# FTDI.net
KiCad netlist of a schematic drawn in Altium Designer
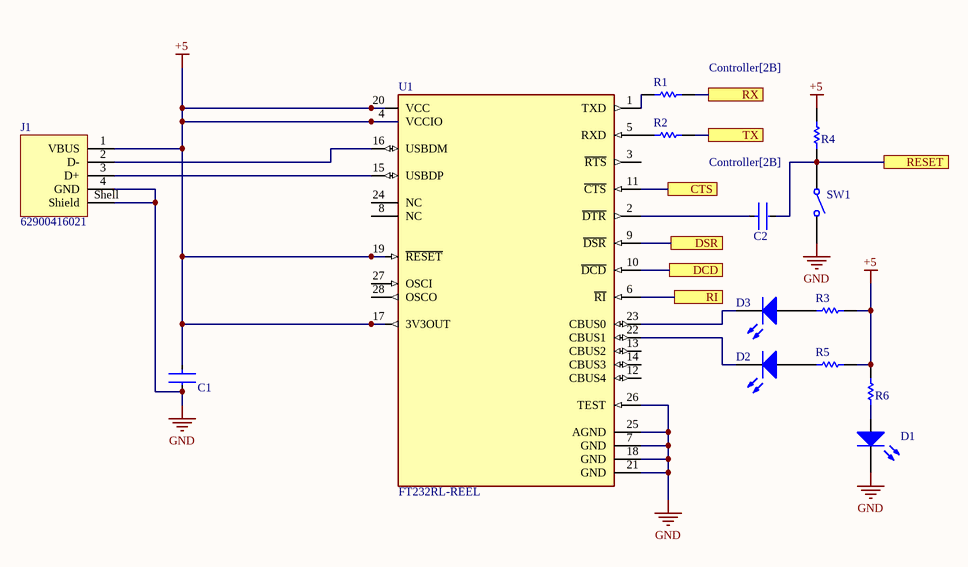
[diagram p0: FTDI.SchDoc]

(export (version "E")
  (design (tool "Eeschema 10.0.6"))
  (components
    (comp (ref "C1")
      (value "GRM188R60J106ME47D")
      (footprint "FP-GRM188-0_1-e0_2_0_55-IPC_A")
      (description "Chip Multilayer Ceramic Capacitors for General Purpose, 0603, 10uF, X5R, 15%, 20%, 6.3V")
      (fields (field (name "VOLTAGE") "6.3V") (field (name "TOLERANCE") "20%"))
      (libsource (lib "Altium Content Vault") (part "02cd4be3c70576c341d710602a673aa"))
    )
    (comp (ref "C2")
      (value "GRM188R60J106ME47D")
      (footprint "FP-GRM188-0_1-e0_2_0_55-IPC_A")
      (description "Chip Multilayer Ceramic Capacitors for General Purpose, 0603, 10uF, X5R, 15%, 20%, 6.3V")
      (fields (field (name "VOLTAGE") "6.3V") (field (name "TOLERANCE") "20%"))
      (libsource (lib "Altium Content Vault") (part "02cd4be3c70576c341d710602a673aa"))
    )
    (comp (ref "D1")
      (value "Light-Emitting Diode")
      (libsource (lib "Simulation Generic Components") (part "LED"))
    )
    (comp (ref "D2")
      (value "Light-Emitting Diode")
      (libsource (lib "Simulation Generic Components") (part "LED"))
    )
    (comp (ref "D3")
      (value "Light-Emitting Diode")
      (libsource (lib "Simulation Generic Components") (part "LED"))
    )
    (comp (ref "J1")
      (value "62900416021")
      (footprint "62900416021")
      (libsource (lib "Altium Content Vault") (part "USB 2.0_Type A_Receptacle_1 Port"))
    )
    (comp (ref "R1")
      (value "CRCW06030000Z0EA")
      (footprint "RESC1609X50X30NL8T20")
      (description "Chip Resistor, 0 Ohm, Jumper, 100 mW, -55 to 155 degC, 0603 (1608 Metric), RoHS, Tape and Reel")
      (fields (field (name "MANUFACTURER") "Vishay Semiconductor"))
      (libsource (lib "Altium Content Vault") (part "RES-2"))
    )
    (comp (ref "R2")
      (value "CRCW06030000Z0EA")
      (footprint "RESC1609X50X30NL8T20")
      (description "Chip Resistor, 0 Ohm, Jumper, 100 mW, -55 to 155 degC, 0603 (1608 Metric), RoHS, Tape and Reel")
      (fields (field (name "MANUFACTURER") "Vishay Semiconductor"))
      (libsource (lib "Altium Content Vault") (part "RES-2"))
    )
    (comp (ref "R3")
      (value "CRCW06030000Z0EA")
      (footprint "RESC1609X50X30NL8T20")
      (description "Chip Resistor, 0 Ohm, Jumper, 100 mW, -55 to 155 degC, 0603 (1608 Metric), RoHS, Tape and Reel")
      (fields (field (name "MANUFACTURER") "Vishay Semiconductor"))
      (libsource (lib "Altium Content Vault") (part "RES-2"))
    )
    (comp (ref "R4")
      (value "CRCW06030000Z0EA")
      (footprint "RESC1609X50X30NL8T20")
      (description "Chip Resistor, 0 Ohm, Jumper, 100 mW, -55 to 155 degC, 0603 (1608 Metric), RoHS, Tape and Reel")
      (fields (field (name "MANUFACTURER") "Vishay Semiconductor"))
      (libsource (lib "Altium Content Vault") (part "RES-2"))
    )
    (comp (ref "R5")
      (value "CRCW06030000Z0EA")
      (footprint "RESC1609X50X30NL8T20")
      (description "Chip Resistor, 0 Ohm, Jumper, 100 mW, -55 to 155 degC, 0603 (1608 Metric), RoHS, Tape and Reel")
      (fields (field (name "MANUFACTURER") "Vishay Semiconductor"))
      (libsource (lib "Altium Content Vault") (part "RES-2"))
    )
    (comp (ref "R6")
      (value "CRCW06030000Z0EA")
      (footprint "RESC1609X50X30NL8T20")
      (description "Chip Resistor, 0 Ohm, Jumper, 100 mW, -55 to 155 degC, 0603 (1608 Metric), RoHS, Tape and Reel")
      (fields (field (name "MANUFACTURER") "Vishay Semiconductor"))
      (libsource (lib "Altium Content Vault") (part "RES-2"))
    )
    (comp (ref "SW1")
      (value "FSMSMTR")
      (footprint "TECO-FSMSMTR_V")
      (description "FSMSM Push Button Switch, 50 mA, -35 to 85 degC, 2-Pin SMD, RoHS, Tape and Reel")
      (fields (field (name "MANUFACTURER") "TE Connectivity"))
      (libsource (lib "Altium Content Vault") (part "SW-SPST-2_C"))
    )
    (comp (ref "U1")
      (value "FT232RL-REEL")
      (footprint "FP-SSOP-28-MFG")
      (description "IC USB FS SERIAL UART 28-SSOP")
      (fields (field (name "VOLTAGE") "5V"))
      (libsource (lib "Altium Content Vault") (part "fa727c664f4d88ca0f1b580aa0dd901"))
    )
  )
  (nets
    (net (code "1") (name "+5") (class "Default")
      (node (ref "C1") (pin "1") (pinfunction "1_1") (pintype "passive"))
      (node (ref "J1") (pin "1") (pinfunction "VBUS_1") (pintype "passive"))
      (node (ref "R3") (pin "2") (pinfunction "2_2") (pintype "passive"))
      (node (ref "R4") (pin "2") (pinfunction "2_2") (pintype "passive"))
      (node (ref "R5") (pin "2") (pinfunction "2_2") (pintype "passive"))
      (node (ref "R6") (pin "2") (pinfunction "2_2") (pintype "passive"))
      (node (ref "U1") (pin "17") (pinfunction "3V3OUT_17") (pintype "output"))
      (node (ref "U1") (pin "19") (pinfunction "~{RESET}_19") (pintype "input"))
      (node (ref "U1") (pin "20") (pinfunction "VCC_20") (pintype "power_in"))
      (node (ref "U1") (pin "4") (pinfunction "VCCIO_4") (pintype "power_in"))
    )
    (net (code "2") (name "/CTS") (class "Default")
      (node (ref "U1") (pin "11") (pinfunction "~{CTS}_11") (pintype "input"))
    )
    (net (code "3") (name "/DCD") (class "Default")
      (node (ref "U1") (pin "10") (pinfunction "~{DCD}_10") (pintype "input"))
    )
    (net (code "4") (name "/DSR") (class "Default")
      (node (ref "U1") (pin "9") (pinfunction "~{DSR}_9") (pintype "input"))
    )
    (net (code "5") (name "/RESET") (class "Default")
      (node (ref "C2") (pin "2") (pinfunction "2_2") (pintype "passive"))
      (node (ref "R4") (pin "1") (pinfunction "1_1") (pintype "passive"))
      (node (ref "SW1") (pin "1") (pinfunction "1_1") (pintype "passive"))
    )
    (net (code "6") (name "/RI") (class "Default")
      (node (ref "U1") (pin "6") (pinfunction "~{RI}_6") (pintype "input"))
    )
    (net (code "7") (name "/RX") (class "Default")
      (node (ref "R1") (pin "2") (pinfunction "2_2") (pintype "passive"))
    )
    (net (code "8") (name "/TX") (class "Default")
      (node (ref "R2") (pin "2") (pinfunction "2_2") (pintype "passive"))
    )
    (net (code "9") (name "GND") (class "Default")
      (node (ref "C1") (pin "2") (pinfunction "2_2") (pintype "passive"))
      (node (ref "D1") (pin "2") (pinfunction "K_2") (pintype "passive"))
      (node (ref "J1") (pin "4") (pinfunction "GND_4") (pintype "passive"))
      (node (ref "J1") (pin "Shell") (pinfunction "Shield_Shell") (pintype "passive"))
      (node (ref "SW1") (pin "2") (pinfunction "2_2") (pintype "passive"))
      (node (ref "U1") (pin "18") (pinfunction "GND_18") (pintype "power_in"))
      (node (ref "U1") (pin "21") (pinfunction "GND_21") (pintype "power_in"))
      (node (ref "U1") (pin "25") (pinfunction "AGND_25") (pintype "power_in"))
      (node (ref "U1") (pin "26") (pinfunction "TEST_26") (pintype "input"))
      (node (ref "U1") (pin "7") (pinfunction "GND_7") (pintype "power_in"))
    )
    (net (code "10") (name "Net-(D1-A)") (class "Default")
      (node (ref "D1") (pin "1") (pinfunction "A_1") (pintype "passive"))
      (node (ref "R6") (pin "1") (pinfunction "1_1") (pintype "passive"))
    )
    (net (code "11") (name "Net-(D2-A)") (class "Default")
      (node (ref "D2") (pin "1") (pinfunction "A_1") (pintype "passive"))
      (node (ref "R5") (pin "1") (pinfunction "1_1") (pintype "passive"))
    )
    (net (code "12") (name "Net-(D2-K)") (class "Default")
      (node (ref "D2") (pin "2") (pinfunction "K_2") (pintype "passive"))
      (node (ref "U1") (pin "22") (pinfunction "CBUS1_22") (pintype "bidirectional"))
    )
    (net (code "13") (name "Net-(D3-A)") (class "Default")
      (node (ref "D3") (pin "1") (pinfunction "A_1") (pintype "passive"))
      (node (ref "R3") (pin "1") (pinfunction "1_1") (pintype "passive"))
    )
    (net (code "14") (name "Net-(D3-K)") (class "Default")
      (node (ref "D3") (pin "2") (pinfunction "K_2") (pintype "passive"))
      (node (ref "U1") (pin "23") (pinfunction "CBUS0_23") (pintype "bidirectional"))
    )
    (net (code "15") (name "Net-(J1-D+)") (class "Default")
      (node (ref "J1") (pin "3") (pinfunction "D+_3") (pintype "passive"))
      (node (ref "U1") (pin "15") (pinfunction "USBDP_15") (pintype "bidirectional"))
    )
    (net (code "16") (name "Net-(J1-D-)") (class "Default")
      (node (ref "J1") (pin "2") (pinfunction "D-_2") (pintype "passive"))
      (node (ref "U1") (pin "16") (pinfunction "USBDM_16") (pintype "bidirectional"))
    )
    (net (code "17") (name "Net-(U1-RXD)") (class "Default")
      (node (ref "R2") (pin "1") (pinfunction "1_1") (pintype "passive"))
      (node (ref "U1") (pin "5") (pinfunction "RXD_5") (pintype "input"))
    )
    (net (code "18") (name "Net-(U1-TXD)") (class "Default")
      (node (ref "R1") (pin "1") (pinfunction "1_1") (pintype "passive"))
      (node (ref "U1") (pin "1") (pinfunction "TXD_1") (pintype "output"))
    )
    (net (code "19") (name "Net-(U1-~{DTR})") (class "Default")
      (node (ref "C2") (pin "1") (pinfunction "1_1") (pintype "passive"))
      (node (ref "U1") (pin "2") (pinfunction "~{DTR}_2") (pintype "output"))
    )
    (net (code "20") (name "unconnected-(U1-CBUS2-Pad13)") (class "Default")
      (node (ref "U1") (pin "13") (pinfunction "CBUS2_13") (pintype "bidirectional"))
    )
    (net (code "21") (name "unconnected-(U1-CBUS3-Pad14)") (class "Default")
      (node (ref "U1") (pin "14") (pinfunction "CBUS3_14") (pintype "bidirectional"))
    )
    (net (code "22") (name "unconnected-(U1-CBUS4-Pad12)") (class "Default")
      (node (ref "U1") (pin "12") (pinfunction "CBUS4_12") (pintype "bidirectional"))
    )
    (net (code "23") (name "unconnected-(U1-NC-Pad8)") (class "Default")
      (node (ref "U1") (pin "8") (pinfunction "NC_8") (pintype "passive"))
    )
    (net (code "24") (name "unconnected-(U1-NC-Pad24)") (class "Default")
      (node (ref "U1") (pin "24") (pinfunction "NC_24") (pintype "passive"))
    )
    (net (code "25") (name "unconnected-(U1-OSCI-Pad27)") (class "Default")
      (node (ref "U1") (pin "27") (pinfunction "OSCI_27") (pintype "input"))
    )
    (net (code "26") (name "unconnected-(U1-OSCO-Pad28)") (class "Default")
      (node (ref "U1") (pin "28") (pinfunction "OSCO_28") (pintype "output"))
    )
    (net (code "27") (name "unconnected-(U1-~{RTS}-Pad3)") (class "Default")
      (node (ref "U1") (pin "3") (pinfunction "~{RTS}_3") (pintype "output"))
    )
  )
)
